# Shared.net
KiCad netlist of a schematic drawn in Altium Designer
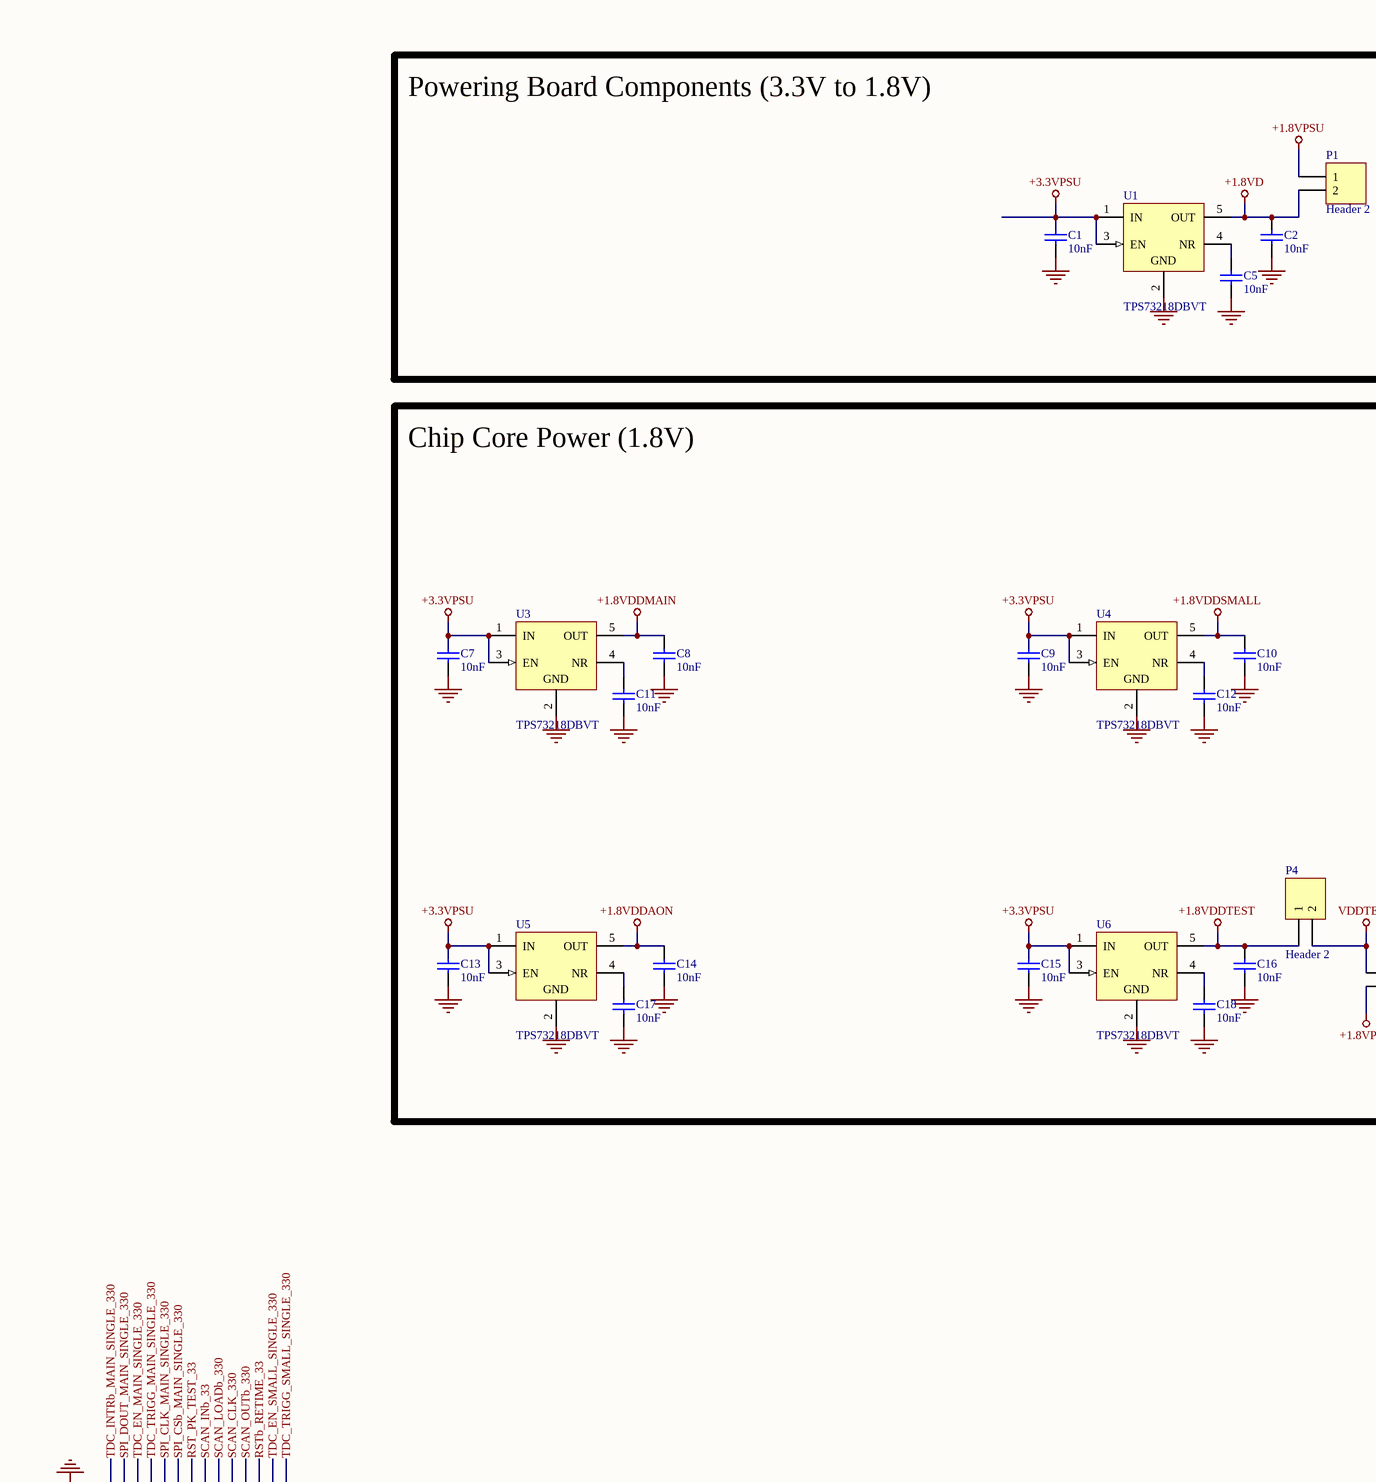
[diagram p0: Shared.SchDoc, top left]
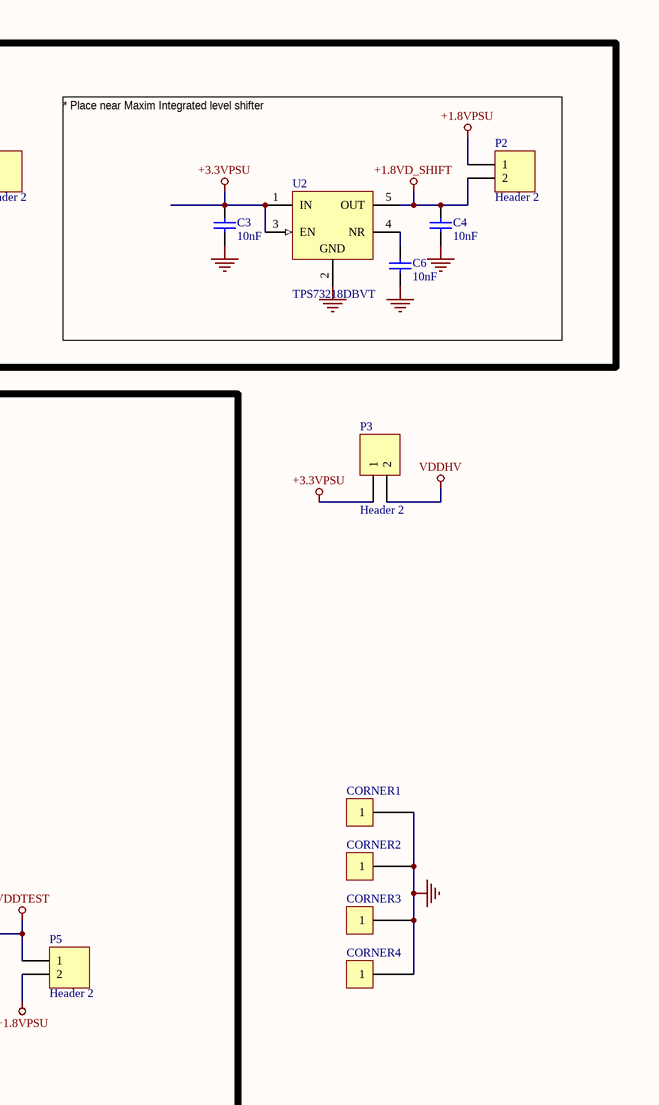
[diagram p1: Shared.SchDoc, top right]
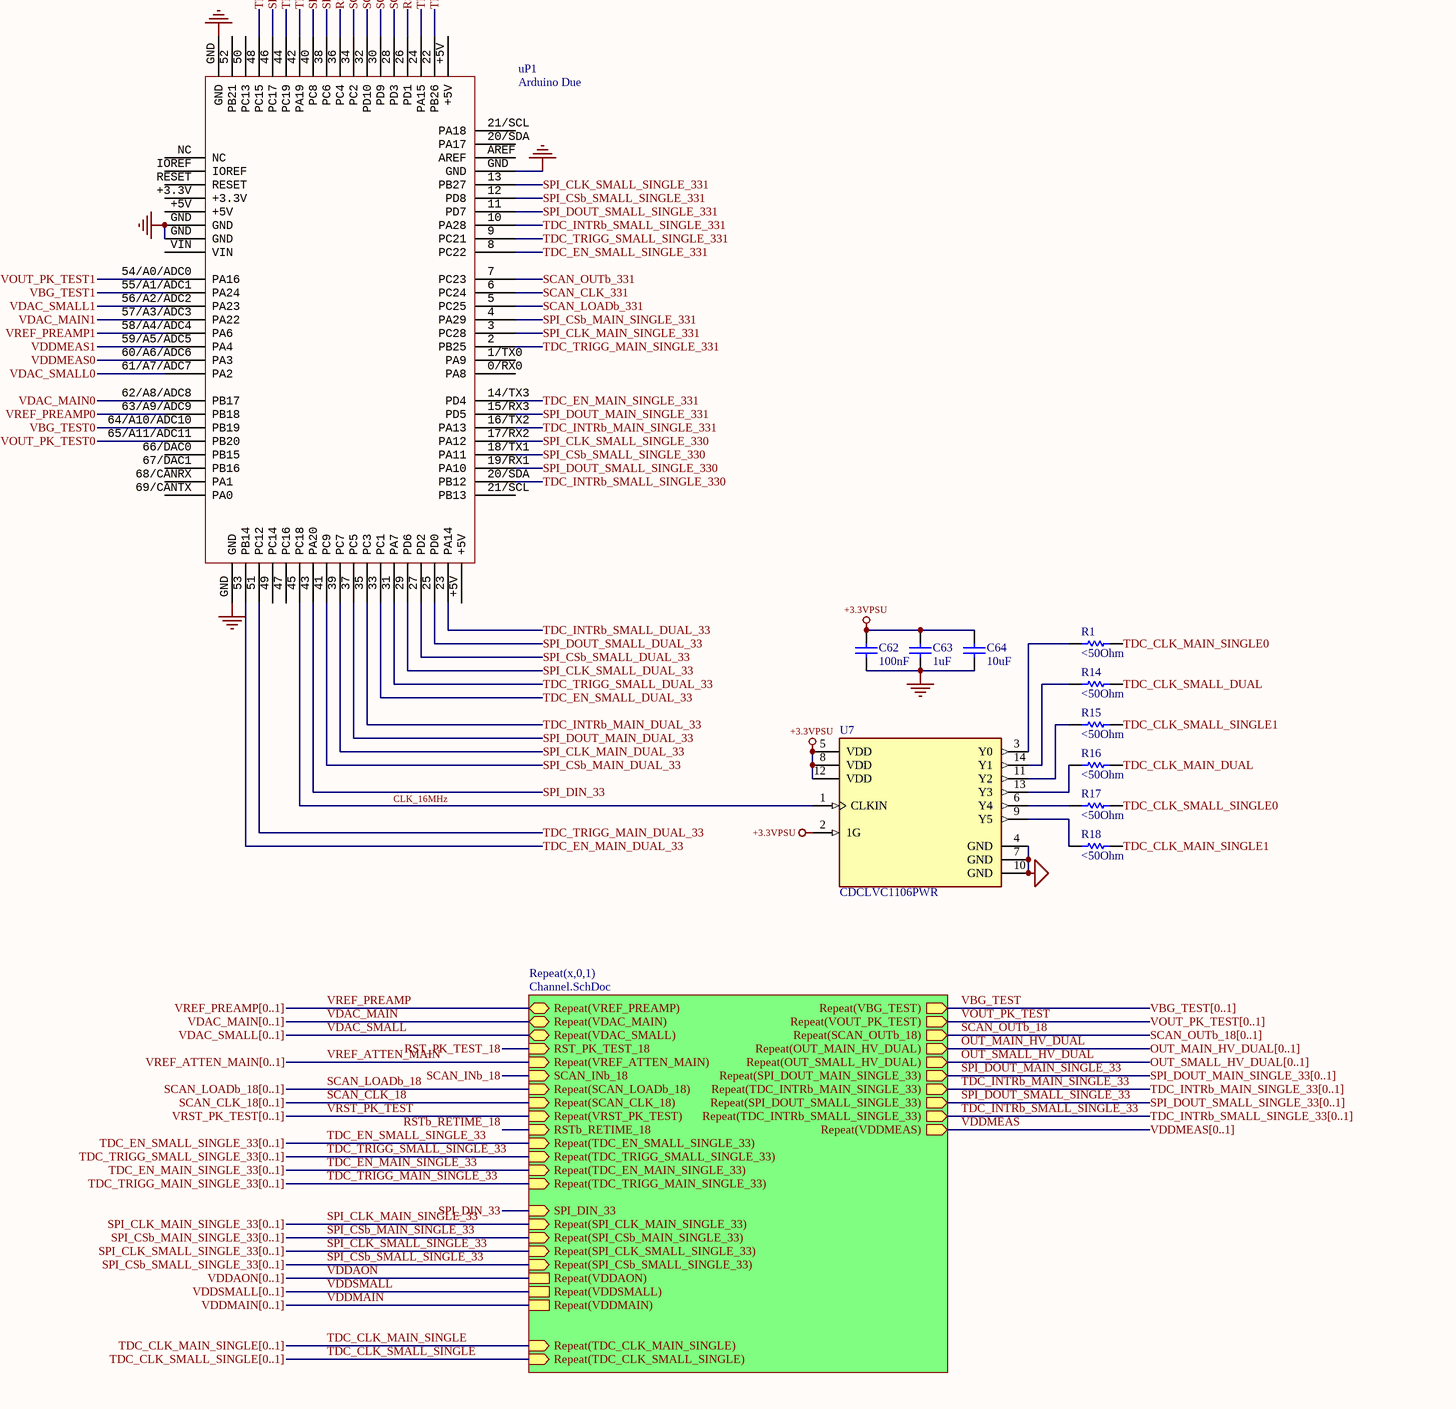
[diagram p2: Shared.SchDoc, bottom left]
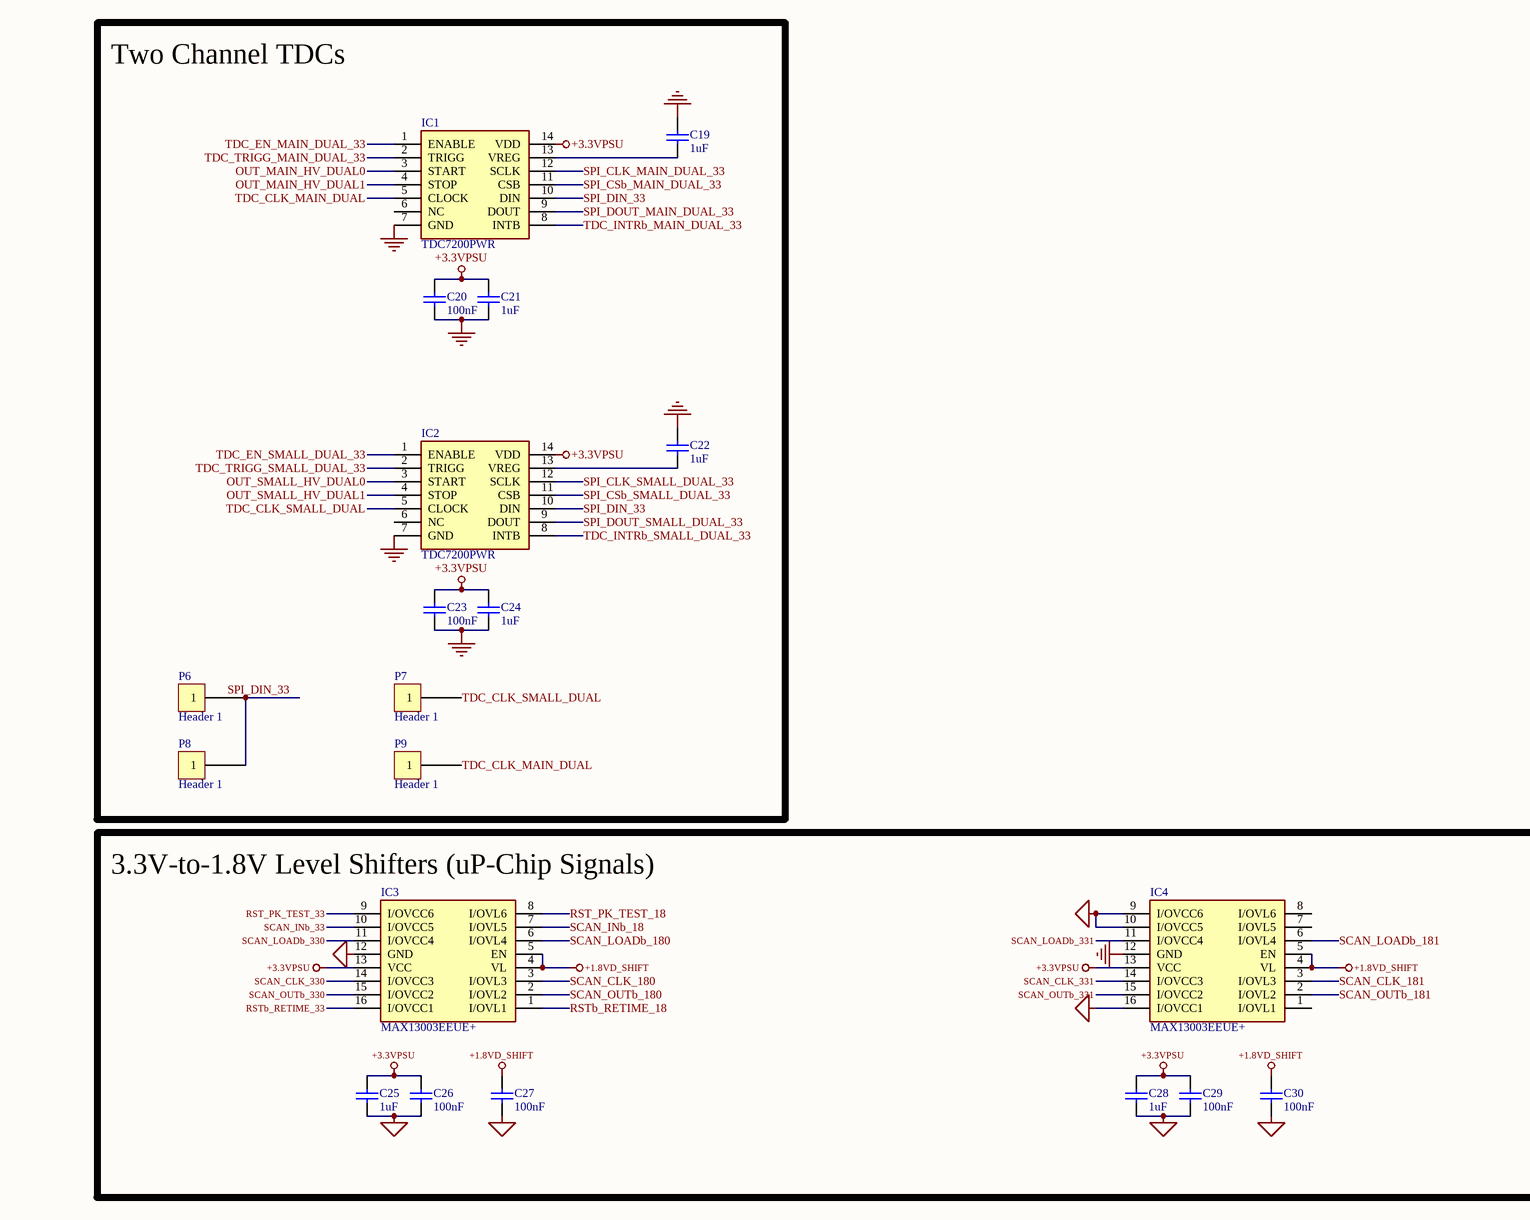
[diagram p3: Shared.SchDoc, bottom right]

(export (version "E")
  (design (tool "Eeschema 10.0.6"))
  (components
    (comp (ref "C1")
      (value "10nF")
      (footprint "CAPC1608X90X35ML10T15")
      (description "0603,10nF")
      (fields (field (name "MANUFACTURER") "Murata"))
      (libsource (lib "Altium Content Vault") (part "CAP-NP-2"))
    )
    (comp (ref "C2")
      (value "10nF")
      (footprint "CAPC1608X90X35ML10T15")
      (description "0603,10nF")
      (fields (field (name "MANUFACTURER") "Murata"))
      (libsource (lib "Altium Content Vault") (part "CAP-NP-2"))
    )
    (comp (ref "C3")
      (value "10nF")
      (footprint "CAPC1608X90X35ML10T15")
      (description "0603,10nF")
      (fields (field (name "MANUFACTURER") "Murata"))
      (libsource (lib "Altium Content Vault") (part "CAP-NP-2"))
    )
    (comp (ref "C4")
      (value "10nF")
      (footprint "CAPC1608X90X35ML10T15")
      (description "0603,10nF")
      (fields (field (name "MANUFACTURER") "Murata"))
      (libsource (lib "Altium Content Vault") (part "CAP-NP-2"))
    )
    (comp (ref "C5")
      (value "10nF")
      (footprint "CAPC1608X90X35ML10T15")
      (description "0603,10nF")
      (fields (field (name "MANUFACTURER") "Murata"))
      (libsource (lib "Altium Content Vault") (part "CAP-NP-2"))
    )
    (comp (ref "C6")
      (value "10nF")
      (footprint "CAPC1608X90X35ML10T15")
      (description "0603,10nF")
      (fields (field (name "MANUFACTURER") "Murata"))
      (libsource (lib "Altium Content Vault") (part "CAP-NP-2"))
    )
    (comp (ref "C7")
      (value "10nF")
      (footprint "CAPC1608X90X35ML10T15")
      (description "0603,10nF")
      (fields (field (name "MANUFACTURER") "Murata"))
      (libsource (lib "Altium Content Vault") (part "CAP-NP-2"))
    )
    (comp (ref "C8")
      (value "10nF")
      (footprint "CAPC1608X90X35ML10T15")
      (description "0603,10nF")
      (fields (field (name "MANUFACTURER") "Murata"))
      (libsource (lib "Altium Content Vault") (part "CAP-NP-2"))
    )
    (comp (ref "C9")
      (value "10nF")
      (footprint "CAPC1608X90X35ML10T15")
      (description "0603,10nF")
      (fields (field (name "MANUFACTURER") "Murata"))
      (libsource (lib "Altium Content Vault") (part "CAP-NP-2"))
    )
    (comp (ref "C10")
      (value "10nF")
      (footprint "CAPC1608X90X35ML10T15")
      (description "0603,10nF")
      (fields (field (name "MANUFACTURER") "Murata"))
      (libsource (lib "Altium Content Vault") (part "CAP-NP-2"))
    )
    (comp (ref "C11")
      (value "10nF")
      (footprint "CAPC1608X90X35ML10T15")
      (description "0603,10nF")
      (fields (field (name "MANUFACTURER") "Murata"))
      (libsource (lib "Altium Content Vault") (part "CAP-NP-2"))
    )
    (comp (ref "C12")
      (value "10nF")
      (footprint "CAPC1608X90X35ML10T15")
      (description "0603,10nF")
      (fields (field (name "MANUFACTURER") "Murata"))
      (libsource (lib "Altium Content Vault") (part "CAP-NP-2"))
    )
    (comp (ref "C13")
      (value "10nF")
      (footprint "CAPC1608X90X35ML10T15")
      (description "0603,10nF")
      (fields (field (name "MANUFACTURER") "Murata"))
      (libsource (lib "Altium Content Vault") (part "CAP-NP-2"))
    )
    (comp (ref "C14")
      (value "10nF")
      (footprint "CAPC1608X90X35ML10T15")
      (description "0603,10nF")
      (fields (field (name "MANUFACTURER") "Murata"))
      (libsource (lib "Altium Content Vault") (part "CAP-NP-2"))
    )
    (comp (ref "C15")
      (value "10nF")
      (footprint "CAPC1608X90X35ML10T15")
      (description "0603,10nF")
      (fields (field (name "MANUFACTURER") "Murata"))
      (libsource (lib "Altium Content Vault") (part "CAP-NP-2"))
    )
    (comp (ref "C16")
      (value "10nF")
      (footprint "CAPC1608X90X35ML10T15")
      (description "0603,10nF")
      (fields (field (name "MANUFACTURER") "Murata"))
      (libsource (lib "Altium Content Vault") (part "CAP-NP-2"))
    )
    (comp (ref "C17")
      (value "10nF")
      (footprint "CAPC1608X90X35ML10T15")
      (description "0603,10nF")
      (fields (field (name "MANUFACTURER") "Murata"))
      (libsource (lib "Altium Content Vault") (part "CAP-NP-2"))
    )
    (comp (ref "C18")
      (value "10nF")
      (footprint "CAPC1608X90X35ML10T15")
      (description "0603,10nF")
      (fields (field (name "MANUFACTURER") "Murata"))
      (libsource (lib "Altium Content Vault") (part "CAP-NP-2"))
    )
    (comp (ref "C19")
      (value "1uF")
      (footprint "CAPC1608X90X35ML10T15")
      (description "0603,1uF")
      (fields (field (name "MANUFACTURER") "Murata"))
      (libsource (lib "Altium Content Vault") (part "CAP-NP-2"))
    )
    (comp (ref "C20")
      (value "100nF")
      (footprint "CAPC1608X90X35ML10T15")
      (description "0603,100nF")
      (fields (field (name "MANUFACTURER") "Murata"))
      (libsource (lib "Altium Content Vault") (part "CAP-NP-2"))
    )
    (comp (ref "C21")
      (value "1uF")
      (footprint "CAPC1608X90X35ML10T15")
      (description "0603,1uF")
      (fields (field (name "MANUFACTURER") "Murata"))
      (libsource (lib "Altium Content Vault") (part "CAP-NP-2"))
    )
    (comp (ref "C22")
      (value "1uF")
      (footprint "CAPC1608X90X35ML10T15")
      (description "0603,1uF")
      (fields (field (name "MANUFACTURER") "Murata"))
      (libsource (lib "Altium Content Vault") (part "CAP-NP-2"))
    )
    (comp (ref "C23")
      (value "100nF")
      (footprint "CAPC1608X90X35ML10T15")
      (description "0603,100nF")
      (fields (field (name "MANUFACTURER") "Murata"))
      (libsource (lib "Altium Content Vault") (part "CAP-NP-2"))
    )
    (comp (ref "C24")
      (value "1uF")
      (footprint "CAPC1608X90X35ML10T15")
      (description "0603,1uF")
      (fields (field (name "MANUFACTURER") "Murata"))
      (libsource (lib "Altium Content Vault") (part "CAP-NP-2"))
    )
    (comp (ref "C25")
      (value "1uF")
      (footprint "CAPC1608X90X35ML10T15")
      (description "0603,1uF")
      (fields (field (name "MANUFACTURER") "Murata"))
      (libsource (lib "Altium Content Vault") (part "CAP-NP-2"))
    )
    (comp (ref "C26")
      (value "100nF")
      (footprint "CAPC1608X90X35ML10T15")
      (description "0603,100nF")
      (fields (field (name "MANUFACTURER") "Murata"))
      (libsource (lib "Altium Content Vault") (part "CAP-NP-2"))
    )
    (comp (ref "C27")
      (value "100nF")
      (footprint "CAPC1608X90X35ML10T15")
      (description "0603,100nF")
      (fields (field (name "MANUFACTURER") "Murata"))
      (libsource (lib "Altium Content Vault") (part "CAP-NP-2"))
    )
    (comp (ref "C28")
      (value "1uF")
      (footprint "CAPC1608X90X35ML10T15")
      (description "0603,1uF")
      (fields (field (name "MANUFACTURER") "Murata"))
      (libsource (lib "Altium Content Vault") (part "CAP-NP-2"))
    )
    (comp (ref "C29")
      (value "100nF")
      (footprint "CAPC1608X90X35ML10T15")
      (description "0603,100nF")
      (fields (field (name "MANUFACTURER") "Murata"))
      (libsource (lib "Altium Content Vault") (part "CAP-NP-2"))
    )
    (comp (ref "C30")
      (value "100nF")
      (footprint "CAPC1608X90X35ML10T15")
      (description "0603,100nF")
      (fields (field (name "MANUFACTURER") "Murata"))
      (libsource (lib "Altium Content Vault") (part "CAP-NP-2"))
    )
    (comp (ref "C62")
      (value "100nF")
      (footprint "CAPC1608X90X35ML10T15")
      (description "0603,100nF")
      (fields (field (name "MANUFACTURER") "Murata"))
      (libsource (lib "Altium Content Vault") (part "CAP-NP-2"))
    )
    (comp (ref "C63")
      (value "1uF")
      (footprint "CAPC1608X90X35ML10T15")
      (description "0603,1uF")
      (fields (field (name "MANUFACTURER") "Murata"))
      (libsource (lib "Altium Content Vault") (part "CAP-NP-2"))
    )
    (comp (ref "C64")
      (value "10uF")
      (footprint "CAPC1608X90X35ML10T15")
      (description "0603,10uF")
      (fields (field (name "MANUFACTURER") "Murata"))
      (libsource (lib "Altium Content Vault") (part "CAP-NP-2"))
    )
    (comp (ref "CORNER1")
      (value "Corner Mount")
      (footprint "CornerMount")
      (libsource (lib "intlib") (part "Corner Mount"))
    )
    (comp (ref "CORNER2")
      (value "Corner Mount")
      (footprint "CornerMount")
      (libsource (lib "intlib") (part "Corner Mount"))
    )
    (comp (ref "CORNER3")
      (value "Corner Mount")
      (footprint "CornerMount")
      (libsource (lib "intlib") (part "Corner Mount"))
    )
    (comp (ref "CORNER4")
      (value "Corner Mount")
      (footprint "CornerMount")
      (libsource (lib "intlib") (part "Corner Mount"))
    )
    (comp (ref "IC1")
      (value "TDC7200PWR")
      (footprint "SamacSys:SOP65P640X120-14N")
      (description "Integrated Circuit")
      (libsource (lib "*") (part "TDC7200PWR"))
    )
    (comp (ref "IC2")
      (value "TDC7200PWR")
      (footprint "SamacSys:SOP65P640X120-14N")
      (description "Integrated Circuit")
      (libsource (lib "*") (part "TDC7200PWR"))
    )
    (comp (ref "IC3")
      (value "MAX13003EEUE+")
      (footprint "SamacSys:SOP65P640X110-16N")
      (description "Integrated Circuit")
      (libsource (lib "*") (part "MAX13003EEUE+"))
    )
    (comp (ref "IC4")
      (value "MAX13003EEUE+")
      (footprint "SamacSys:SOP65P640X110-16N")
      (description "Integrated Circuit")
      (libsource (lib "*") (part "MAX13003EEUE+"))
    )
    (comp (ref "P1")
      (value "Header 2")
      (footprint "HDR1X2")
      (description "Header, 2-Pin")
      (fields (field (name "PUBLISHER") "Altium Limited"))
      (libsource (lib "Miscellaneous Connectors") (part "Header 2"))
    )
    (comp (ref "P2")
      (value "Header 2")
      (footprint "HDR1X2")
      (description "Header, 2-Pin")
      (fields (field (name "PUBLISHER") "Altium Limited"))
      (libsource (lib "Miscellaneous Connectors") (part "Header 2"))
    )
    (comp (ref "P3")
      (value "Header 2")
      (footprint "HDR1X2")
      (description "Header, 2-Pin")
      (fields (field (name "PUBLISHER") "Altium Limited"))
      (libsource (lib "") (part "Header 2_1"))
    )
    (comp (ref "P4")
      (value "Header 2")
      (footprint "HDR1X2")
      (description "Header, 2-Pin")
      (fields (field (name "PUBLISHER") "Altium Limited"))
      (libsource (lib "") (part "Header 2_1"))
    )
    (comp (ref "P5")
      (value "Header 2")
      (footprint "HDR1X2")
      (description "Header, 2-Pin")
      (fields (field (name "PUBLISHER") "Altium Limited"))
      (libsource (lib "Miscellaneous Connectors") (part "Header 2"))
    )
    (comp (ref "P6") (value "Header 1") (footprint "Header1") (libsource (lib "intlib") (part "Header 1")))
    (comp (ref "P7") (value "Header 1") (footprint "Header1") (libsource (lib "intlib") (part "Header 1")))
    (comp (ref "P8") (value "Header 1") (footprint "Header1") (libsource (lib "intlib") (part "Header 1")))
    (comp (ref "P9") (value "Header 1") (footprint "Header1") (libsource (lib "intlib") (part "Header 1")))
    (comp (ref "R1")
      (value "<50Ohm")
      (footprint "RESC1609X50X30NL8T20")
      (description "0603,<50Ohm")
      (fields (field (name "MANUFACTURER") "Vishay Semiconductor"))
      (libsource (lib "Altium Content Vault") (part "RES-2"))
    )
    (comp (ref "R14")
      (value "<50Ohm")
      (footprint "RESC1609X50X30NL8T20")
      (description "0603,<50Ohm")
      (fields (field (name "MANUFACTURER") "Vishay Semiconductor"))
      (libsource (lib "Altium Content Vault") (part "RES-2"))
    )
    (comp (ref "R15")
      (value "<50Ohm")
      (footprint "RESC1609X50X30NL8T20")
      (description "0603,<50Ohm")
      (fields (field (name "MANUFACTURER") "Vishay Semiconductor"))
      (libsource (lib "Altium Content Vault") (part "RES-2"))
    )
    (comp (ref "R16")
      (value "<50Ohm")
      (footprint "RESC1609X50X30NL8T20")
      (description "0603,<50Ohm")
      (fields (field (name "MANUFACTURER") "Vishay Semiconductor"))
      (libsource (lib "Altium Content Vault") (part "RES-2"))
    )
    (comp (ref "R17")
      (value "<50Ohm")
      (footprint "RESC1609X50X30NL8T20")
      (description "0603,<50Ohm")
      (fields (field (name "MANUFACTURER") "Vishay Semiconductor"))
      (libsource (lib "Altium Content Vault") (part "RES-2"))
    )
    (comp (ref "R18")
      (value "<50Ohm")
      (footprint "RESC1609X50X30NL8T20")
      (description "0603,<50Ohm")
      (fields (field (name "MANUFACTURER") "Vishay Semiconductor"))
      (libsource (lib "Altium Content Vault") (part "RES-2"))
    )
    (comp (ref "U1")
      (value "TPS73218DBVT")
      (footprint "DBV0005A_N")
      (fields (field (name "MANUFACTURER") "Texas Instruments"))
      (libsource (lib "Altium Content Vault") (part "TI-TPS79NXX-YYSOT5"))
    )
    (comp (ref "U2")
      (value "TPS73218DBVT")
      (footprint "DBV0005A_N")
      (fields (field (name "MANUFACTURER") "Texas Instruments"))
      (libsource (lib "Altium Content Vault") (part "TI-TPS79NXX-YYSOT5"))
    )
    (comp (ref "U3")
      (value "TPS73218DBVT")
      (footprint "DBV0005A_N")
      (fields (field (name "MANUFACTURER") "Texas Instruments"))
      (libsource (lib "Altium Content Vault") (part "TI-TPS79NXX-YYSOT5"))
    )
    (comp (ref "U4")
      (value "TPS73218DBVT")
      (footprint "DBV0005A_N")
      (fields (field (name "MANUFACTURER") "Texas Instruments"))
      (libsource (lib "Altium Content Vault") (part "TI-TPS79NXX-YYSOT5"))
    )
    (comp (ref "U5")
      (value "TPS73218DBVT")
      (footprint "DBV0005A_N")
      (fields (field (name "MANUFACTURER") "Texas Instruments"))
      (libsource (lib "Altium Content Vault") (part "TI-TPS79NXX-YYSOT5"))
    )
    (comp (ref "U6")
      (value "TPS73218DBVT")
      (footprint "DBV0005A_N")
      (fields (field (name "MANUFACTURER") "Texas Instruments"))
      (libsource (lib "Altium Content Vault") (part "TI-TPS79NXX-YYSOT5"))
    )
    (comp (ref "U7")
      (value "CDCLVC1106PWR")
      (footprint "FP-PW0014A-MFG")
      (description "IC CLK BUFFER 1:6 250MHZ 14TSSOP")
      (fields
        (field (name "MANUFACTURER") "Texas Instruments")
        (field (name "OCTOPART") "https://octopart.com/cdclvc1106pwr-texas+instruments-18629865")
      )
      (libsource (lib "Altium Content Vault") (part "c658b08e815d5ba30375de9a23295a1"))
    )
    (comp (ref "uP1")
      (value "Arduino Due")
      (footprint "Arduino Due")
      (description "Header, 10-pin, 8-pin (4x), 18-pin dual row")
      (libsource (lib "intlib") (part "Arduino Due"))
    )
  )
  (nets
    (net (code "11") (name "+1.8VD") (class "Default")
      (node (ref "C2") (pin "1") (pinfunction "1_1") (pintype "passive"))
      (node (ref "P1") (pin "2") (pinfunction "2_2") (pintype "passive"))
      (node (ref "U1") (pin "5") (pinfunction "OUT_5") (pintype "power_in"))
    )
    (net (code "12") (name "+1.8VDDAON") (class "Default")
      (node (ref "C14") (pin "1") (pinfunction "1_1") (pintype "passive"))
      (node (ref "U5") (pin "5") (pinfunction "OUT_5") (pintype "power_in"))
    )
    (net (code "13") (name "+1.8VDDMAIN") (class "Default")
      (node (ref "C8") (pin "1") (pinfunction "1_1") (pintype "passive"))
      (node (ref "U3") (pin "5") (pinfunction "OUT_5") (pintype "power_in"))
    )
    (net (code "14") (name "+1.8VDDSMALL") (class "Default")
      (node (ref "C10") (pin "1") (pinfunction "1_1") (pintype "passive"))
      (node (ref "U4") (pin "5") (pinfunction "OUT_5") (pintype "power_in"))
    )
    (net (code "15") (name "+1.8VDDTEST") (class "Default")
      (node (ref "C16") (pin "1") (pinfunction "1_1") (pintype "passive"))
      (node (ref "P4") (pin "1") (pinfunction "1_1") (pintype "passive"))
      (node (ref "U6") (pin "5") (pinfunction "OUT_5") (pintype "power_in"))
    )
    (net (code "16") (name "+1.8VD_SHIFT") (class "Default")
      (node (ref "C27") (pin "1") (pinfunction "1_1") (pintype "passive"))
      (node (ref "C30") (pin "1") (pinfunction "1_1") (pintype "passive"))
      (node (ref "C4") (pin "1") (pinfunction "1_1") (pintype "passive"))
      (node (ref "IC3") (pin "4") (pinfunction "VL_4") (pintype "passive"))
      (node (ref "IC3") (pin "5") (pinfunction "EN_5") (pintype "passive"))
      (node (ref "IC4") (pin "4") (pinfunction "VL_4") (pintype "passive"))
      (node (ref "IC4") (pin "5") (pinfunction "EN_5") (pintype "passive"))
      (node (ref "P2") (pin "2") (pinfunction "2_2") (pintype "passive"))
      (node (ref "U2") (pin "5") (pinfunction "OUT_5") (pintype "power_in"))
    )
    (net (code "17") (name "+1.8VPSU") (class "Default")
      (node (ref "P1") (pin "1") (pinfunction "1_1") (pintype "passive"))
      (node (ref "P2") (pin "1") (pinfunction "1_1") (pintype "passive"))
      (node (ref "P5") (pin "2") (pinfunction "2_2") (pintype "passive"))
    )
    (net (code "18") (name "+3.3VPSU") (class "Default")
      (node (ref "C1") (pin "1") (pinfunction "1_1") (pintype "passive"))
      (node (ref "C13") (pin "1") (pinfunction "1_1") (pintype "passive"))
      (node (ref "C15") (pin "1") (pinfunction "1_1") (pintype "passive"))
      (node (ref "C20") (pin "1") (pinfunction "1_1") (pintype "passive"))
      (node (ref "C21") (pin "1") (pinfunction "1_1") (pintype "passive"))
      (node (ref "C23") (pin "1") (pinfunction "1_1") (pintype "passive"))
      (node (ref "C24") (pin "1") (pinfunction "1_1") (pintype "passive"))
      (node (ref "C25") (pin "2") (pinfunction "2_2") (pintype "passive"))
      (node (ref "C26") (pin "2") (pinfunction "2_2") (pintype "passive"))
      (node (ref "C28") (pin "2") (pinfunction "2_2") (pintype "passive"))
      (node (ref "C29") (pin "2") (pinfunction "2_2") (pintype "passive"))
      (node (ref "C3") (pin "1") (pinfunction "1_1") (pintype "passive"))
      (node (ref "C62") (pin "1") (pinfunction "1_1") (pintype "passive"))
      (node (ref "C63") (pin "1") (pinfunction "1_1") (pintype "passive"))
      (node (ref "C64") (pin "1") (pinfunction "1_1") (pintype "passive"))
      (node (ref "C7") (pin "1") (pinfunction "1_1") (pintype "passive"))
      (node (ref "C9") (pin "1") (pinfunction "1_1") (pintype "passive"))
      (node (ref "IC1") (pin "14") (pinfunction "VDD_14") (pintype "passive"))
      (node (ref "IC2") (pin "14") (pinfunction "VDD_14") (pintype "passive"))
      (node (ref "IC3") (pin "13") (pinfunction "VCC_13") (pintype "passive"))
      (node (ref "IC4") (pin "13") (pinfunction "VCC_13") (pintype "passive"))
      (node (ref "P3") (pin "1") (pinfunction "1_1") (pintype "passive"))
      (node (ref "U1") (pin "1") (pinfunction "IN_1") (pintype "power_in"))
      (node (ref "U1") (pin "3") (pinfunction "EN_3") (pintype "input"))
      (node (ref "U2") (pin "1") (pinfunction "IN_1") (pintype "power_in"))
      (node (ref "U2") (pin "3") (pinfunction "EN_3") (pintype "input"))
      (node (ref "U3") (pin "1") (pinfunction "IN_1") (pintype "power_in"))
      (node (ref "U3") (pin "3") (pinfunction "EN_3") (pintype "input"))
      (node (ref "U4") (pin "1") (pinfunction "IN_1") (pintype "power_in"))
      (node (ref "U4") (pin "3") (pinfunction "EN_3") (pintype "input"))
      (node (ref "U5") (pin "1") (pinfunction "IN_1") (pintype "power_in"))
      (node (ref "U5") (pin "3") (pinfunction "EN_3") (pintype "input"))
      (node (ref "U6") (pin "1") (pinfunction "IN_1") (pintype "power_in"))
      (node (ref "U6") (pin "3") (pinfunction "EN_3") (pintype "input"))
      (node (ref "U7") (pin "12") (pinfunction "VDD_12") (pintype "power_in"))
      (node (ref "U7") (pin "2") (pinfunction "1G_2") (pintype "input"))
      (node (ref "U7") (pin "5") (pinfunction "VDD_5") (pintype "power_in"))
      (node (ref "U7") (pin "8") (pinfunction "VDD_8") (pintype "power_in"))
    )
    (net (code "19") (name "/CLK_16MHz") (class "Default")
      (node (ref "U7") (pin "1") (pinfunction "CLKIN_1") (pintype "input"))
      (node (ref "uP1") (pin "45") (pinfunction "PC18_45") (pintype "passive"))
    )
    (net (code "21") (name "/OUT_MAIN_HV_DUAL0") (class "Default")
      (node (ref "IC1") (pin "3") (pinfunction "START_3") (pintype "passive"))
    )
    (net (code "22") (name "/OUT_MAIN_HV_DUAL1") (class "Default")
      (node (ref "IC1") (pin "4") (pinfunction "STOP_4") (pintype "passive"))
    )
    (net (code "25") (name "/OUT_SMALL_HV_DUAL0") (class "Default")
      (node (ref "IC2") (pin "3") (pinfunction "START_3") (pintype "passive"))
    )
    (net (code "26") (name "/OUT_SMALL_HV_DUAL1") (class "Default")
      (node (ref "IC2") (pin "4") (pinfunction "STOP_4") (pintype "passive"))
    )
    (net (code "28") (name "/RST_PK_TEST_18") (class "Default")
      (node (ref "IC3") (pin "8") (pinfunction "I/OVL6_8") (pintype "passive"))
    )
    (net (code "29") (name "/RST_PK_TEST_33") (class "Default")
      (node (ref "IC3") (pin "9") (pinfunction "I/OVCC6_9") (pintype "passive"))
      (node (ref "uP1") (pin "36") (pinfunction "PC4_36") (pintype "passive"))
    )
    (net (code "30") (name "/RSTb_RETIME_18") (class "Default")
      (node (ref "IC3") (pin "1") (pinfunction "I/OVL1_1") (pintype "passive"))
    )
    (net (code "31") (name "/RSTb_RETIME_33") (class "Default")
      (node (ref "IC3") (pin "16") (pinfunction "I/OVCC1_16") (pintype "passive"))
      (node (ref "uP1") (pin "26") (pinfunction "PD1_26") (pintype "passive"))
    )
    (net (code "34") (name "/SCAN_CLK_180") (class "Default")
      (node (ref "IC3") (pin "3") (pinfunction "I/OVL3_3") (pintype "passive"))
    )
    (net (code "35") (name "/SCAN_CLK_181") (class "Default")
      (node (ref "IC4") (pin "3") (pinfunction "I/OVL3_3") (pintype "passive"))
    )
    (net (code "36") (name "/SCAN_CLK_330") (class "Default")
      (node (ref "IC3") (pin "14") (pinfunction "I/OVCC3_14") (pintype "passive"))
      (node (ref "uP1") (pin "30") (pinfunction "PD9_30") (pintype "passive"))
    )
    (net (code "37") (name "/SCAN_CLK_331") (class "Default")
      (node (ref "IC4") (pin "14") (pinfunction "I/OVCC3_14") (pintype "passive"))
      (node (ref "uP1") (pin "6") (pinfunction "PC24_6") (pintype "passive"))
    )
    (net (code "38") (name "/SCAN_INb_18") (class "Default")
      (node (ref "IC3") (pin "7") (pinfunction "I/OVL5_7") (pintype "passive"))
    )
    (net (code "39") (name "/SCAN_INb_33") (class "Default")
      (node (ref "IC3") (pin "10") (pinfunction "I/OVCC5_10") (pintype "passive"))
      (node (ref "uP1") (pin "34") (pinfunction "PC2_34") (pintype "passive"))
    )
    (net (code "42") (name "/SCAN_LOADb_180") (class "Default")
      (node (ref "IC3") (pin "6") (pinfunction "I/OVL4_6") (pintype "passive"))
    )
    (net (code "43") (name "/SCAN_LOADb_181") (class "Default")
      (node (ref "IC4") (pin "6") (pinfunction "I/OVL4_6") (pintype "passive"))
    )
    (net (code "44") (name "/SCAN_LOADb_330") (class "Default")
      (node (ref "IC3") (pin "11") (pinfunction "I/OVCC4_11") (pintype "passive"))
      (node (ref "uP1") (pin "32") (pinfunction "PD10_32") (pintype "passive"))
    )
    (net (code "45") (name "/SCAN_LOADb_331") (class "Default")
      (node (ref "IC4") (pin "11") (pinfunction "I/OVCC4_11") (pintype "passive"))
      (node (ref "uP1") (pin "5") (pinfunction "PC25_5") (pintype "passive"))
    )
    (net (code "48") (name "/SCAN_OUTb_180") (class "Default")
      (node (ref "IC3") (pin "2") (pinfunction "I/OVL2_2") (pintype "passive"))
    )
    (net (code "49") (name "/SCAN_OUTb_181") (class "Default")
      (node (ref "IC4") (pin "2") (pinfunction "I/OVL2_2") (pintype "passive"))
    )
    (net (code "50") (name "/SCAN_OUTb_330") (class "Default")
      (node (ref "IC3") (pin "15") (pinfunction "I/OVCC2_15") (pintype "passive"))
      (node (ref "uP1") (pin "28") (pinfunction "PD3_28") (pintype "passive"))
    )
    (net (code "51") (name "/SCAN_OUTb_331") (class "Default")
      (node (ref "IC4") (pin "15") (pinfunction "I/OVCC2_15") (pintype "passive"))
      (node (ref "uP1") (pin "7") (pinfunction "PC23_7") (pintype "passive"))
    )
    (net (code "52") (name "/SPI_CLK_MAIN_DUAL_33") (class "Default")
      (node (ref "IC1") (pin "12") (pinfunction "SCLK_12") (pintype "passive"))
      (node (ref "uP1") (pin "39") (pinfunction "PC7_39") (pintype "passive"))
    )
    (net (code "55") (name "/SPI_CLK_MAIN_SINGLE_330") (class "Default")
      (node (ref "uP1") (pin "40") (pinfunction "PC8_40") (pintype "passive"))
    )
    (net (code "56") (name "/SPI_CLK_MAIN_SINGLE_331") (class "Default")
      (node (ref "uP1") (pin "3") (pinfunction "PC28_3") (pintype "passive"))
    )
    (net (code "57") (name "/SPI_CLK_SMALL_DUAL_33") (class "Default")
      (node (ref "IC2") (pin "12") (pinfunction "SCLK_12") (pintype "passive"))
      (node (ref "uP1") (pin "29") (pinfunction "PD6_29") (pintype "passive"))
    )
    (net (code "60") (name "/SPI_CLK_SMALL_SINGLE_330") (class "Default")
      (node (ref "uP1") (pin "17/RX2") (pinfunction "PA12_17/RX2") (pintype "passive"))
    )
    (net (code "61") (name "/SPI_CLK_SMALL_SINGLE_331") (class "Default")
      (node (ref "uP1") (pin "13") (pinfunction "PB27_13") (pintype "passive"))
    )
    (net (code "62") (name "/SPI_CSb_MAIN_DUAL_33") (class "Default")
      (node (ref "IC1") (pin "11") (pinfunction "CSB_11") (pintype "passive"))
      (node (ref "uP1") (pin "41") (pinfunction "PC9_41") (pintype "passive"))
    )
    (net (code "65") (name "/SPI_CSb_MAIN_SINGLE_330") (class "Default")
      (node (ref "uP1") (pin "38") (pinfunction "PC6_38") (pintype "passive"))
    )
    (net (code "66") (name "/SPI_CSb_MAIN_SINGLE_331") (class "Default")
      (node (ref "uP1") (pin "4") (pinfunction "PA29_4") (pintype "passive"))
    )
    (net (code "67") (name "/SPI_CSb_SMALL_DUAL_33") (class "Default")
      (node (ref "IC2") (pin "11") (pinfunction "CSB_11") (pintype "passive"))
      (node (ref "uP1") (pin "27") (pinfunction "PD2_27") (pintype "passive"))
    )
    (net (code "70") (name "/SPI_CSb_SMALL_SINGLE_330") (class "Default")
      (node (ref "uP1") (pin "18/TX1") (pinfunction "PA11_18/TX1") (pintype "passive"))
    )
    (net (code "71") (name "/SPI_CSb_SMALL_SINGLE_331") (class "Default")
      (node (ref "uP1") (pin "12") (pinfunction "PD8_12") (pintype "passive"))
    )
    (net (code "72") (name "/SPI_DIN_33") (class "Default")
      (node (ref "IC1") (pin "10") (pinfunction "DIN_10") (pintype "passive"))
      (node (ref "IC2") (pin "10") (pinfunction "DIN_10") (pintype "passive"))
      (node (ref "P6") (pin "1") (pinfunction "1_1") (pintype "passive"))
      (node (ref "P8") (pin "1") (pinfunction "1_1") (pintype "passive"))
      (node (ref "uP1") (pin "43") (pinfunction "PA20_43") (pintype "passive"))
    )
    (net (code "73") (name "/SPI_DOUT_MAIN_DUAL_33") (class "Default")
      (node (ref "IC1") (pin "9") (pinfunction "DOUT_9") (pintype "passive"))
      (node (ref "uP1") (pin "37") (pinfunction "PC5_37") (pintype "passive"))
    )
    (net (code "76") (name "/SPI_DOUT_MAIN_SINGLE_330") (class "Default")
      (node (ref "uP1") (pin "46") (pinfunction "PC17_46") (pintype "passive"))
    )
    (net (code "77") (name "/SPI_DOUT_MAIN_SINGLE_331") (class "Default")
      (node (ref "uP1") (pin "15/RX3") (pinfunction "PD5_15/RX3") (pintype "passive"))
    )
    (net (code "78") (name "/SPI_DOUT_SMALL_DUAL_33") (class "Default")
      (node (ref "IC2") (pin "9") (pinfunction "DOUT_9") (pintype "passive"))
      (node (ref "uP1") (pin "25") (pinfunction "PD0_25") (pintype "passive"))
    )
    (net (code "81") (name "/SPI_DOUT_SMALL_SINGLE_330") (class "Default")
      (node (ref "uP1") (pin "19/RX1") (pinfunction "PA10_19/RX1") (pintype "passive"))
    )
    (net (code "82") (name "/SPI_DOUT_SMALL_SINGLE_331") (class "Default")
      (node (ref "uP1") (pin "11") (pinfunction "PD7_11") (pintype "passive"))
    )
    (net (code "83") (name "/TDC_CLK_MAIN_DUAL") (class "Default")
      (node (ref "IC1") (pin "5") (pinfunction "CLOCK_5") (pintype "passive"))
      (node (ref "P9") (pin "1") (pinfunction "1_1") (pintype "passive"))
      (node (ref "R16") (pin "1") (pinfunction "1_1") (pintype "passive"))
    )
    (net (code "85") (name "/TDC_CLK_MAIN_SINGLE0") (class "Default")
      (node (ref "R1") (pin "1") (pinfunction "1_1") (pintype "passive"))
    )
    (net (code "86") (name "/TDC_CLK_MAIN_SINGLE1") (class "Default")
      (node (ref "R18") (pin "1") (pinfunction "1_1") (pintype "passive"))
    )
    (net (code "88") (name "/TDC_CLK_SMALL_DUAL") (class "Default")
      (node (ref "IC2") (pin "5") (pinfunction "CLOCK_5") (pintype "passive"))
      (node (ref "P7") (pin "1") (pinfunction "1_1") (pintype "passive"))
      (node (ref "R14") (pin "1") (pinfunction "1_1") (pintype "passive"))
    )
    (net (code "90") (name "/TDC_CLK_SMALL_SINGLE0") (class "Default")
      (node (ref "R17") (pin "1") (pinfunction "1_1") (pintype "passive"))
    )
    (net (code "91") (name "/TDC_CLK_SMALL_SINGLE1") (class "Default")
      (node (ref "R15") (pin "1") (pinfunction "1_1") (pintype "passive"))
    )
    (net (code "93") (name "/TDC_EN_MAIN_DUAL_33") (class "Default")
      (node (ref "IC1") (pin "1") (pinfunction "ENABLE_1") (pintype "passive"))
      (node (ref "uP1") (pin "53") (pinfunction "PB14_53") (pintype "passive"))
    )
    (net (code "96") (name "/TDC_EN_MAIN_SINGLE_330") (class "Default")
      (node (ref "uP1") (pin "44") (pinfunction "PC19_44") (pintype "passive"))
    )
    (net (code "97") (name "/TDC_EN_MAIN_SINGLE_331") (class "Default")
      (node (ref "uP1") (pin "14/TX3") (pinfunction "PD4_14/TX3") (pintype "passive"))
    )
    (net (code "98") (name "/TDC_EN_SMALL_DUAL_33") (class "Default")
      (node (ref "IC2") (pin "1") (pinfunction "ENABLE_1") (pintype "passive"))
      (node (ref "uP1") (pin "33") (pinfunction "PC1_33") (pintype "passive"))
    )
    (net (code "101") (name "/TDC_EN_SMALL_SINGLE_330") (class "Default")
      (node (ref "uP1") (pin "24") (pinfunction "PA15_24") (pintype "passive"))
    )
    (net (code "102") (name "/TDC_EN_SMALL_SINGLE_331") (class "Default")
      (node (ref "uP1") (pin "8") (pinfunction "PC22_8") (pintype "passive"))
    )
    (net (code "103") (name "/TDC_INTRb_MAIN_DUAL_33") (class "Default")
      (node (ref "IC1") (pin "8") (pinfunction "INTB_8") (pintype "passive"))
      (node (ref "uP1") (pin "35") (pinfunction "PC3_35") (pintype "passive"))
    )
    (net (code "106") (name "/TDC_INTRb_MAIN_SINGLE_330") (class "Default")
      (node (ref "uP1") (pin "48") (pinfunction "PC15_48") (pintype "passive"))
    )
    (net (code "107") (name "/TDC_INTRb_MAIN_SINGLE_331") (class "Default")
      (node (ref "uP1") (pin "16/TX2") (pinfunction "PA13_16/TX2") (pintype "passive"))
    )
    (net (code "108") (name "/TDC_INTRb_SMALL_DUAL_33") (class "Default")
      (node (ref "IC2") (pin "8") (pinfunction "INTB_8") (pintype "passive"))
      (node (ref "uP1") (pin "23") (pinfunction "PA14_23") (pintype "passive"))
    )
    (net (code "111") (name "/TDC_INTRb_SMALL_SINGLE_330") (class "Default")
      (node (ref "uP1") (pin "20/SDA") (pinfunction "PB12_20/SDA") (pintype "passive"))
    )
    (net (code "112") (name "/TDC_INTRb_SMALL_SINGLE_331") (class "Default")
      (node (ref "uP1") (pin "10") (pinfunction "PA28_10") (pintype "passive"))
    )
    (net (code "113") (name "/TDC_TRIGG_MAIN_DUAL_33") (class "Default")
      (node (ref "IC1") (pin "2") (pinfunction "TRIGG_2") (pintype "passive"))
      (node (ref "uP1") (pin "51") (pinfunction "PC12_51") (pintype "passive"))
    )
    (net (code "116") (name "/TDC_TRIGG_MAIN_SINGLE_330") (class "Default")
      (node (ref "uP1") (pin "42") (pinfunction "PA19_42") (pintype "passive"))
    )
    (net (code "117") (name "/TDC_TRIGG_MAIN_SINGLE_331") (class "Default")
      (node (ref "uP1") (pin "2") (pinfunction "PB25_2") (pintype "passive"))
    )
    (net (code "118") (name "/TDC_TRIGG_SMALL_DUAL_33") (class "Default")
      (node (ref "IC2") (pin "2") (pinfunction "TRIGG_2") (pintype "passive"))
      (node (ref "uP1") (pin "31") (pinfunction "PA7_31") (pintype "passive"))
    )
    (net (code "121") (name "/TDC_TRIGG_SMALL_SINGLE_330") (class "Default")
      (node (ref "uP1") (pin "22") (pinfunction "PB26_22") (pintype "passive"))
    )
    (net (code "122") (name "/TDC_TRIGG_SMALL_SINGLE_331") (class "Default")
      (node (ref "uP1") (pin "9") (pinfunction "PC21_9") (pintype "passive"))
    )
    (net (code "124") (name "/VBG_TEST0") (class "Default")
      (node (ref "uP1") (pin "64/A10/ADC10") (pinfunction "PB19_64/A10/ADC10") (pintype "passive"))
    )
    (net (code "125") (name "/VBG_TEST1") (class "Default")
      (node (ref "uP1") (pin "55/A1/ADC1") (pinfunction "PA24_55/A1/ADC1") (pintype "passive"))
    )
    (net (code "128") (name "/VDAC_MAIN0") (class "Default")
      (node (ref "uP1") (pin "62/A8/ADC8") (pinfunction "PB17_62/A8/ADC8") (pintype "passive"))
    )
    (net (code "129") (name "/VDAC_MAIN1") (class "Default")
      (node (ref "uP1") (pin "57/A3/ADC3") (pinfunction "PA22_57/A3/ADC3") (pintype "passive"))
    )
    (net (code "132") (name "/VDAC_SMALL0") (class "Default")
      (node (ref "uP1") (pin "61/A7/ADC7") (pinfunction "PA2_61/A7/ADC7") (pintype "passive"))
    )
    (net (code "133") (name "/VDAC_SMALL1") (class "Default")
      (node (ref "uP1") (pin "56/A2/ADC2") (pinfunction "PA23_56/A2/ADC2") (pintype "passive"))
    )
    (net (code "140") (name "/VDDMEAS0") (class "Default")
      (node (ref "uP1") (pin "60/A6/ADC6") (pinfunction "PA3_60/A6/ADC6") (pintype "passive"))
    )
    (net (code "141") (name "/VDDMEAS1") (class "Default")
      (node (ref "uP1") (pin "59/A5/ADC5") (pinfunction "PA4_59/A5/ADC5") (pintype "passive"))
    )
    (net (code "146") (name "/VOUT_PK_TEST0") (class "Default")
      (node (ref "uP1") (pin "65/A11/ADC11") (pinfunction "PB20_65/A11/ADC11") (pintype "passive"))
    )
    (net (code "147") (name "/VOUT_PK_TEST1") (class "Default")
      (node (ref "uP1") (pin "54/A0/ADC0") (pinfunction "PA16_54/A0/ADC0") (pintype "passive"))
    )
    (net (code "152") (name "/VREF_PREAMP0") (class "Default")
      (node (ref "uP1") (pin "63/A9/ADC9") (pinfunction "PB18_63/A9/ADC9") (pintype "passive"))
    )
    (net (code "153") (name "/VREF_PREAMP1") (class "Default")
      (node (ref "uP1") (pin "58/A4/ADC4") (pinfunction "PA6_58/A4/ADC4") (pintype "passive"))
    )
    (net (code "157") (name "GND") (class "Default")
      (node (ref "C1") (pin "2") (pinfunction "2_2") (pintype "passive"))
      (node (ref "C10") (pin "2") (pinfunction "2_2") (pintype "passive"))
      (node (ref "C11") (pin "2") (pinfunction "2_2") (pintype "passive"))
      (node (ref "C12") (pin "2") (pinfunction "2_2") (pintype "passive"))
      (node (ref "C13") (pin "2") (pinfunction "2_2") (pintype "passive"))
      (node (ref "C14") (pin "2") (pinfunction "2_2") (pintype "passive"))
      (node (ref "C15") (pin "2") (pinfunction "2_2") (pintype "passive"))
      (node (ref "C16") (pin "2") (pinfunction "2_2") (pintype "passive"))
      (node (ref "C17") (pin "2") (pinfunction "2_2") (pintype "passive"))
      (node (ref "C18") (pin "2") (pinfunction "2_2") (pintype "passive"))
      (node (ref "C19") (pin "2") (pinfunction "2_2") (pintype "passive"))
      (node (ref "C2") (pin "2") (pinfunction "2_2") (pintype "passive"))
      (node (ref "C20") (pin "2") (pinfunction "2_2") (pintype "passive"))
      (node (ref "C21") (pin "2") (pinfunction "2_2") (pintype "passive"))
      (node (ref "C22") (pin "2") (pinfunction "2_2") (pintype "passive"))
      (node (ref "C23") (pin "2") (pinfunction "2_2") (pintype "passive"))
      (node (ref "C24") (pin "2") (pinfunction "2_2") (pintype "passive"))
      (node (ref "C25") (pin "1") (pinfunction "1_1") (pintype "passive"))
      (node (ref "C26") (pin "1") (pinfunction "1_1") (pintype "passive"))
      (node (ref "C27") (pin "2") (pinfunction "2_2") (pintype "passive"))
      (node (ref "C28") (pin "1") (pinfunction "1_1") (pintype "passive"))
      (node (ref "C29") (pin "1") (pinfunction "1_1") (pintype "passive"))
      (node (ref "C3") (pin "2") (pinfunction "2_2") (pintype "passive"))
      (node (ref "C30") (pin "2") (pinfunction "2_2") (pintype "passive"))
      (node (ref "C4") (pin "2") (pinfunction "2_2") (pintype "passive"))
      (node (ref "C5") (pin "2") (pinfunction "2_2") (pintype "passive"))
      (node (ref "C6") (pin "2") (pinfunction "2_2") (pintype "passive"))
      (node (ref "C62") (pin "2") (pinfunction "2_2") (pintype "passive"))
      (node (ref "C63") (pin "2") (pinfunction "2_2") (pintype "passive"))
      (node (ref "C64") (pin "2") (pinfunction "2_2") (pintype "passive"))
      (node (ref "C7") (pin "2") (pinfunction "2_2") (pintype "passive"))
      (node (ref "C8") (pin "2") (pinfunction "2_2") (pintype "passive"))
      (node (ref "C9") (pin "2") (pinfunction "2_2") (pintype "passive"))
      (node (ref "CORNER1") (pin "1") (pinfunction "1_1") (pintype "passive"))
      (node (ref "CORNER2") (pin "1") (pinfunction "1_1") (pintype "passive"))
      (node (ref "CORNER3") (pin "1") (pinfunction "1_1") (pintype "passive"))
      (node (ref "CORNER4") (pin "1") (pinfunction "1_1") (pintype "passive"))
      (node (ref "IC1") (pin "7") (pinfunction "GND_7") (pintype "passive"))
      (node (ref "IC2") (pin "7") (pinfunction "GND_7") (pintype "passive"))
      (node (ref "IC3") (pin "12") (pinfunction "GND_12") (pintype "passive"))
      (node (ref "IC4") (pin "10") (pinfunction "I/OVCC5_10") (pintype "passive"))
      (node (ref "IC4") (pin "12") (pinfunction "GND_12") (pintype "passive"))
      (node (ref "IC4") (pin "16") (pinfunction "I/OVCC1_16") (pintype "passive"))
      (node (ref "IC4") (pin "9") (pinfunction "I/OVCC6_9") (pintype "passive"))
      (node (ref "U1") (pin "2") (pinfunction "GND_2") (pintype "power_in"))
      (node (ref "U2") (pin "2") (pinfunction "GND_2") (pintype "power_in"))
      (node (ref "U3") (pin "2") (pinfunction "GND_2") (pintype "power_in"))
      (node (ref "U4") (pin "2") (pinfunction "GND_2") (pintype "power_in"))
      (node (ref "U5") (pin "2") (pinfunction "GND_2") (pintype "power_in"))
      (node (ref "U6") (pin "2") (pinfunction "GND_2") (pintype "power_in"))
      (node (ref "U7") (pin "10") (pinfunction "GND_10") (pintype "power_in"))
      (node (ref "U7") (pin "4") (pinfunction "GND_4") (pintype "power_in"))
      (node (ref "U7") (pin "7") (pinfunction "GND_7") (pintype "power_in"))
      (node (ref "uP1") (pin "GND") (pinfunction "GND_GND") (pintype "passive"))
    )
    (net (code "158") (name "Net-(IC1-VREG)") (class "Default")
      (node (ref "C19") (pin "1") (pinfunction "1_1") (pintype "passive"))
      (node (ref "IC1") (pin "13") (pinfunction "VREG_13") (pintype "passive"))
    )
    (net (code "159") (name "Net-(IC2-VREG)") (class "Default")
      (node (ref "C22") (pin "1") (pinfunction "1_1") (pintype "passive"))
      (node (ref "IC2") (pin "13") (pinfunction "VREG_13") (pintype "passive"))
    )
    (net (code "160") (name "Net-(U1-NR)") (class "Default")
      (node (ref "C5") (pin "1") (pinfunction "1_1") (pintype "passive"))
      (node (ref "U1") (pin "4") (pinfunction "NR_4") (pintype "passive"))
    )
    (net (code "161") (name "Net-(U2-NR)") (class "Default")
      (node (ref "C6") (pin "1") (pinfunction "1_1") (pintype "passive"))
      (node (ref "U2") (pin "4") (pinfunction "NR_4") (pintype "passive"))
    )
    (net (code "162") (name "Net-(U3-NR)") (class "Default")
      (node (ref "C11") (pin "1") (pinfunction "1_1") (pintype "passive"))
      (node (ref "U3") (pin "4") (pinfunction "NR_4") (pintype "passive"))
    )
    (net (code "163") (name "Net-(U4-NR)") (class "Default")
      (node (ref "C12") (pin "1") (pinfunction "1_1") (pintype "passive"))
      (node (ref "U4") (pin "4") (pinfunction "NR_4") (pintype "passive"))
    )
    (net (code "164") (name "Net-(U5-NR)") (class "Default")
      (node (ref "C17") (pin "1") (pinfunction "1_1") (pintype "passive"))
      (node (ref "U5") (pin "4") (pinfunction "NR_4") (pintype "passive"))
    )
    (net (code "165") (name "Net-(U6-NR)") (class "Default")
      (node (ref "C18") (pin "1") (pinfunction "1_1") (pintype "passive"))
      (node (ref "U6") (pin "4") (pinfunction "NR_4") (pintype "passive"))
    )
    (net (code "166") (name "Net-(U7-Y0)") (class "Default")
      (node (ref "R1") (pin "2") (pinfunction "2_2") (pintype "passive"))
      (node (ref "U7") (pin "3") (pinfunction "Y0_3") (pintype "output"))
    )
    (net (code "167") (name "Net-(U7-Y1)") (class "Default")
      (node (ref "R14") (pin "2") (pinfunction "2_2") (pintype "passive"))
      (node (ref "U7") (pin "14") (pinfunction "Y1_14") (pintype "output"))
    )
    (net (code "168") (name "Net-(U7-Y2)") (class "Default")
      (node (ref "R15") (pin "2") (pinfunction "2_2") (pintype "passive"))
      (node (ref "U7") (pin "11") (pinfunction "Y2_11") (pintype "output"))
    )
    (net (code "169") (name "Net-(U7-Y3)") (class "Default")
      (node (ref "R16") (pin "2") (pinfunction "2_2") (pintype "passive"))
      (node (ref "U7") (pin "13") (pinfunction "Y3_13") (pintype "output"))
    )
    (net (code "170") (name "Net-(U7-Y4)") (class "Default")
      (node (ref "R17") (pin "2") (pinfunction "2_2") (pintype "passive"))
      (node (ref "U7") (pin "6") (pinfunction "Y4_6") (pintype "output"))
    )
    (net (code "171") (name "Net-(U7-Y5)") (class "Default")
      (node (ref "R18") (pin "2") (pinfunction "2_2") (pintype "passive"))
      (node (ref "U7") (pin "9") (pinfunction "Y5_9") (pintype "output"))
    )
    (net (code "172") (name "VDDHV") (class "Default")
      (node (ref "P3") (pin "2") (pinfunction "2_2") (pintype "passive"))
    )
    (net (code "173") (name "VDDTEST") (class "Default")
      (node (ref "P4") (pin "2") (pinfunction "2_2") (pintype "passive"))
      (node (ref "P5") (pin "1") (pinfunction "1_1") (pintype "passive"))
    )
    (net (code "174") (name "unconnected-(IC1-NC-Pad6)") (class "Default")
      (node (ref "IC1") (pin "6") (pinfunction "NC_6") (pintype "passive"))
    )
    (net (code "175") (name "unconnected-(IC2-NC-Pad6)") (class "Default")
      (node (ref "IC2") (pin "6") (pinfunction "NC_6") (pintype "passive"))
    )
    (net (code "176") (name "unconnected-(IC4-I{slash}OVL1-Pad1)") (class "Default")
      (node (ref "IC4") (pin "1") (pinfunction "I/OVL1_1") (pintype "passive"))
    )
    (net (code "177") (name "unconnected-(IC4-I{slash}OVL5-Pad7)") (class "Default")
      (node (ref "IC4") (pin "7") (pinfunction "I/OVL5_7") (pintype "passive"))
    )
    (net (code "178") (name "unconnected-(IC4-I{slash}OVL6-Pad8)") (class "Default")
      (node (ref "IC4") (pin "8") (pinfunction "I/OVL6_8") (pintype "passive"))
    )
    (net (code "179") (name "unconnected-(uP1-PA0-Pad69{slash}CANTX)") (class "Default")
      (node (ref "uP1") (pin "69/CANTX") (pinfunction "PA0_69/CANTX") (pintype "passive"))
    )
    (net (code "180") (name "unconnected-(uP1-PA1-Pad68{slash}CANRX)") (class "Default")
      (node (ref "uP1") (pin "68/CANRX") (pinfunction "PA1_68/CANRX") (pintype "passive"))
    )
    (net (code "181") (name "unconnected-(uP1-PA8-Pad0{slash}RX0)") (class "Default")
      (node (ref "uP1") (pin "0/RX0") (pinfunction "PA8_0/RX0") (pintype "passive"))
    )
    (net (code "182") (name "unconnected-(uP1-PA9-Pad1{slash}TX0)") (class "Default")
      (node (ref "uP1") (pin "1/TX0") (pinfunction "PA9_1/TX0") (pintype "passive"))
    )
    (net (code "183") (name "unconnected-(uP1-PA17-Pad20{slash}SDA)") (class "Default")
      (node (ref "uP1") (pin "20/SDA") (pinfunction "PA17_20/SDA") (pintype "passive"))
    )
    (net (code "184") (name "unconnected-(uP1-PA18-Pad21{slash}SCL)") (class "Default")
      (node (ref "uP1") (pin "21/SCL") (pinfunction "PA18_21/SCL") (pintype "passive"))
    )
    (net (code "185") (name "unconnected-(uP1-PB13-Pad21{slash}SCL)") (class "Default")
      (node (ref "uP1") (pin "21/SCL") (pinfunction "PB13_21/SCL") (pintype "passive"))
    )
    (net (code "186") (name "unconnected-(uP1-PB15-Pad66{slash}DAC0)") (class "Default")
      (node (ref "uP1") (pin "66/DAC0") (pinfunction "PB15_66/DAC0") (pintype "passive"))
    )
    (net (code "187") (name "unconnected-(uP1-PB16-Pad67{slash}DAC1)") (class "Default")
      (node (ref "uP1") (pin "67/DAC1") (pinfunction "PB16_67/DAC1") (pintype "passive"))
    )
    (net (code "188") (name "unconnected-(uP1-PB21-Pad52)") (class "Default")
      (node (ref "uP1") (pin "52") (pinfunction "PB21_52") (pintype "passive"))
    )
    (net (code "189") (name "unconnected-(uP1-PC13-Pad50)") (class "Default")
      (node (ref "uP1") (pin "50") (pinfunction "PC13_50") (pintype "passive"))
    )
    (net (code "190") (name "unconnected-(uP1-PC14-Pad49)") (class "Default")
      (node (ref "uP1") (pin "49") (pinfunction "PC14_49") (pintype "passive"))
    )
    (net (code "191") (name "unconnected-(uP1-PC16-Pad47)") (class "Default")
      (node (ref "uP1") (pin "47") (pinfunction "PC16_47") (pintype "passive"))
    )
    (net (code "192") (name "unconnected-(uP1-Pad+3.3V)") (class "Default")
      (node (ref "uP1") (pin "+3.3V") (pinfunction "+3.3V_+3.3V") (pintype "passive"))
    )
    (net (code "193") (name "unconnected-(uP1-Pad+5V)") (class "Default")
      (node (ref "uP1") (pin "+5V") (pinfunction "+5V_+5V") (pintype "passive"))
    )
    (net (code "194") (name "unconnected-(uP1-Pad+5V)_1") (class "Default")
      (node (ref "uP1") (pin "+5V") (pinfunction "+5V_+5V") (pintype "passive"))
    )
    (net (code "195") (name "unconnected-(uP1-Pad+5V)_2") (class "Default")
      (node (ref "uP1") (pin "+5V") (pinfunction "+5V_+5V") (pintype "passive"))
    )
    (net (code "196") (name "unconnected-(uP1-PadAREF)") (class "Default")
      (node (ref "uP1") (pin "AREF") (pinfunction "AREF_AREF") (pintype "passive"))
    )
    (net (code "197") (name "unconnected-(uP1-PadIOREF)") (class "Default")
      (node (ref "uP1") (pin "IOREF") (pinfunction "IOREF_IOREF") (pintype "passive"))
    )
    (net (code "198") (name "unconnected-(uP1-PadNC)") (class "Default")
      (node (ref "uP1") (pin "NC") (pinfunction "NC_NC") (pintype "passive"))
    )
    (net (code "199") (name "unconnected-(uP1-PadRESET)") (class "Default")
      (node (ref "uP1") (pin "RESET") (pinfunction "RESET_RESET") (pintype "passive"))
    )
    (net (code "200") (name "unconnected-(uP1-PadVIN)") (class "Default")
      (node (ref "uP1") (pin "VIN") (pinfunction "VIN_VIN") (pintype "passive"))
    )
  )
)
